# kombee.net
KiCad netlist of a schematic drawn in EAGLE
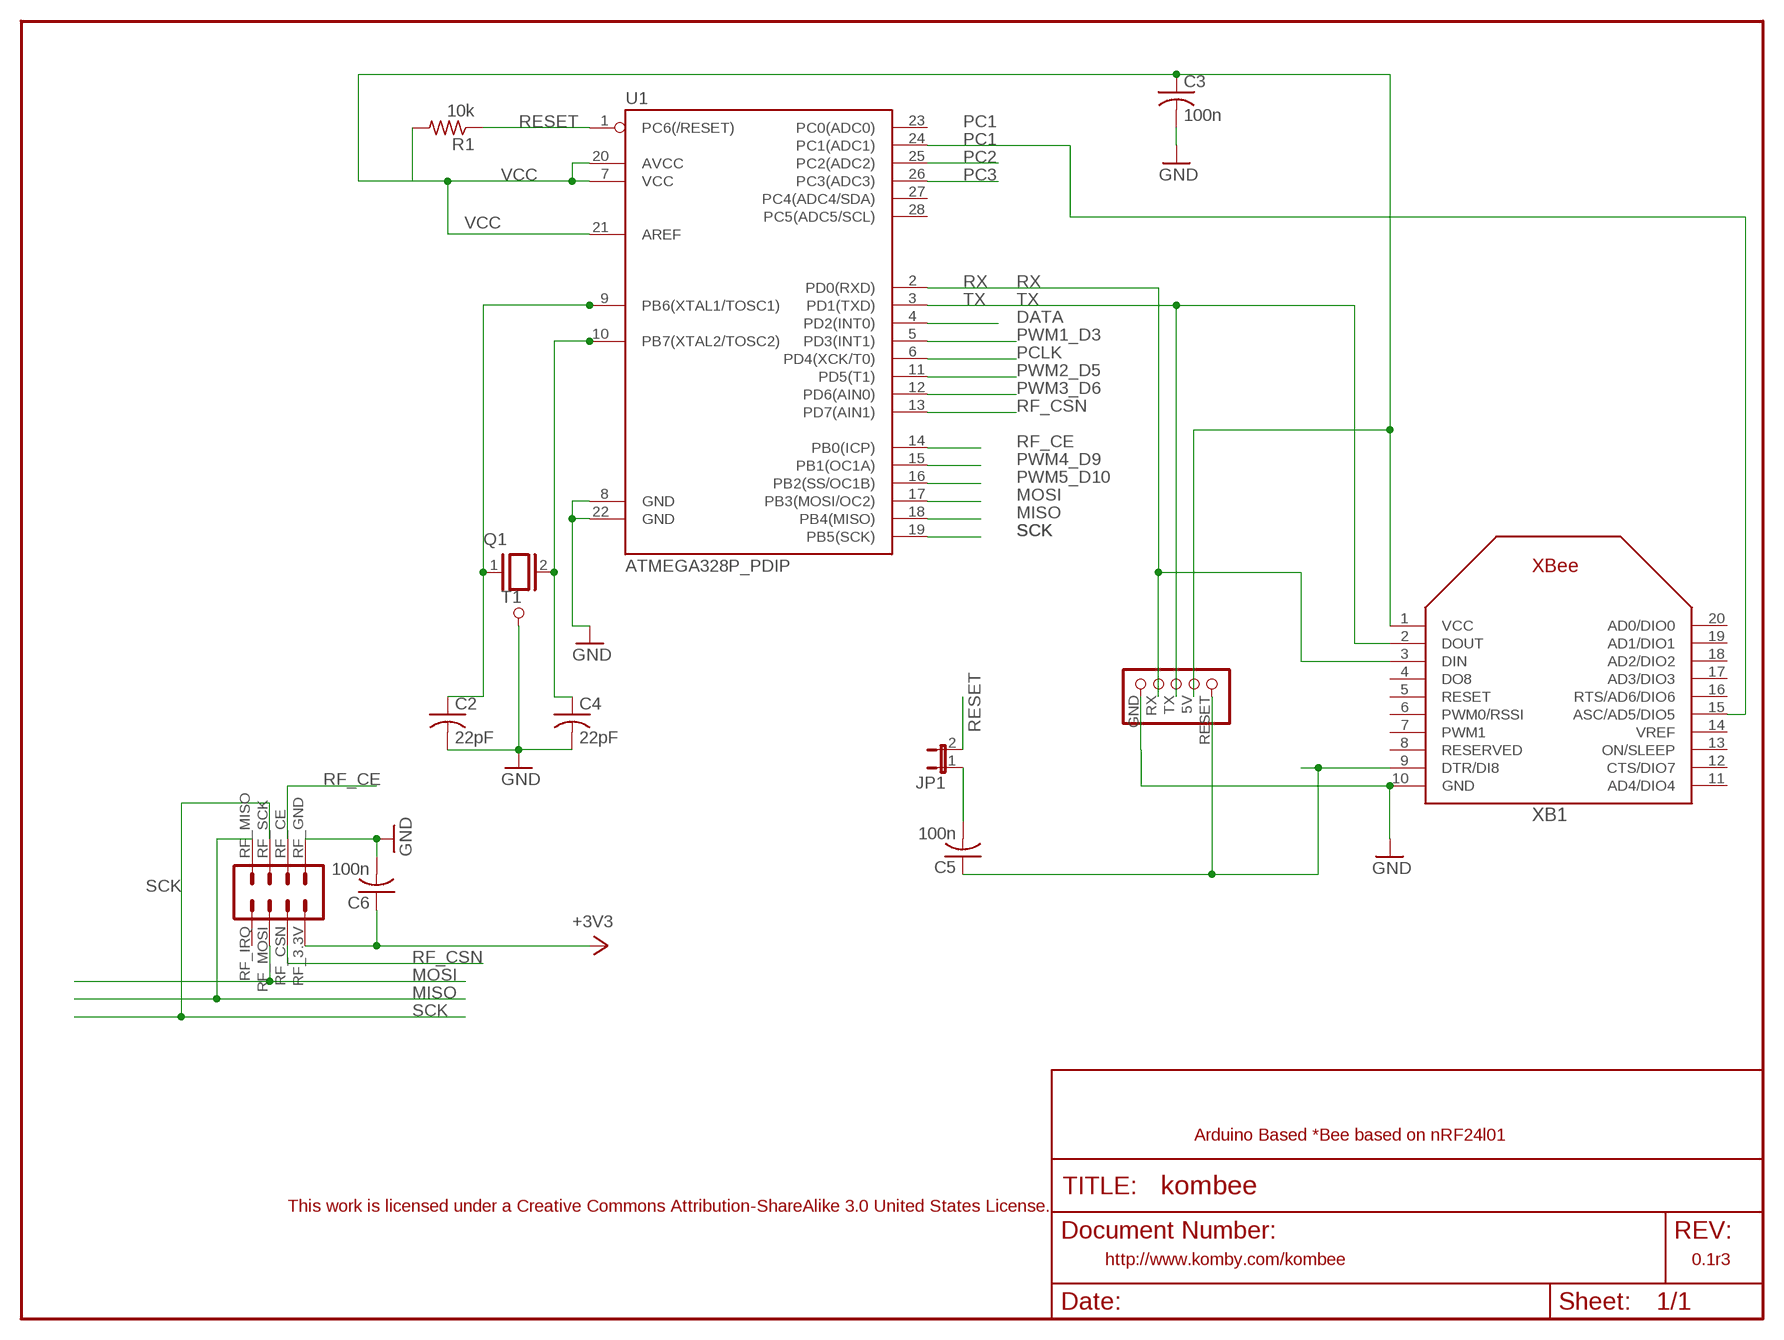
[diagram p0: schematic, sheet 1]

(export (version "E")
  (design (tool "Eeschema 10.0.6"))
  (components
    (comp (ref "C2")
      (value "22pF")
      (footprint "eagle-import:C0805K")
      (libsource (lib "eagle-import") (part "C-USC0805K"))
    )
    (comp (ref "C3")
      (value "100n")
      (footprint "eagle-import:C025-025X050")
      (libsource (lib "eagle-import") (part "C-US025-025X050"))
    )
    (comp (ref "C4")
      (value "22pF")
      (footprint "eagle-import:C0805K")
      (libsource (lib "eagle-import") (part "C-USC0805K"))
    )
    (comp (ref "C5")
      (value "100n")
      (footprint "eagle-import:C025-025X050")
      (libsource (lib "eagle-import") (part "C-US025-025X050"))
    )
    (comp (ref "C6")
      (value "100n")
      (footprint "eagle-import:C025-025X050")
      (libsource (lib "eagle-import") (part "C-US025-025X050"))
    )
    (comp (ref "JP1")
      (value "JP1E")
      (footprint "eagle-import:JP1")
      (libsource (lib "eagle-import") (part "JP1E"))
    )
    (comp (ref "Q1")
      (value "XTAL/S")
      (footprint "eagle-import:QS")
      (libsource (lib "eagle-import") (part "XTAL/S"))
    )
    (comp (ref "R1")
      (value "10k")
      (footprint "eagle-import:0204_7")
      (libsource (lib "eagle-import") (part "R-US_0204/7"))
    )
    (comp (ref "T1")
      (value "PAD_TERMINAL-1.02MM_ROUND")
      (footprint "eagle-import:CON_PAD_ROUND_1.02MM")
      (libsource (lib "eagle-import") (part "PAD_TERMINAL-1.02MM_ROUND"))
    )
    (comp (ref "U$1")
      (value "NRF24L01_HEADER")
      (footprint "eagle-import:NRF24L01")
      (libsource (lib "eagle-import") (part "NRF24L01_HEADER"))
    )
    (comp (ref "U$2")
      (value "KOMBY_TTL_SERIAL")
      (footprint "eagle-import:KOMBY_SERIAL_FOOTPRINT")
      (libsource (lib "eagle-import") (part "KOMBY_TTL_SERIAL"))
    )
    (comp (ref "U1")
      (value "ATMEGA328P_PDIP")
      (footprint "eagle-import:DIL28-3")
      (libsource (lib "eagle-import") (part "ATMEGA328P_PDIP"))
    )
    (comp (ref "XB1")
      (value "XBEE")
      (footprint "eagle-import:XBEE")
      (libsource (lib "eagle-import") (part "XBEE"))
    )
  )
  (nets
    (net (code "1") (name "+3V3") (class "Default")
      (node (ref "C3") (pin "1") (pinfunction "1_1") (pintype "passive"))
      (node (ref "C6") (pin "1") (pinfunction "1_1") (pintype "passive"))
      (node (ref "R1") (pin "2") (pinfunction "2_2") (pintype "passive"))
      (node (ref "U$1") (pin "RF_3.3V") (pinfunction "RF_3.3V_RF_3.3V") (pintype "passive"))
      (node (ref "U$2") (pin "5V") (pinfunction "5V_5V") (pintype "passive"))
      (node (ref "U1") (pin "20") (pinfunction "AVCC_20") (pintype "bidirectional"))
      (node (ref "U1") (pin "21") (pinfunction "AREF_21") (pintype "bidirectional"))
      (node (ref "U1") (pin "7") (pinfunction "VCC_7") (pintype "bidirectional"))
      (node (ref "XB1") (pin "1") (pinfunction "VCC_1") (pintype "power_in"))
    )
    (net (code "2") (name "/DATA") (class "Default")
      (node (ref "U1") (pin "4") (pinfunction "PD2(INT0)_4") (pintype "bidirectional"))
    )
    (net (code "3") (name "/MISO") (class "Default")
      (node (ref "U$1") (pin "RF_MISO") (pinfunction "RF_MISO_RF_MISO") (pintype "passive"))
      (node (ref "U1") (pin "18") (pinfunction "PB4(MISO)_18") (pintype "bidirectional"))
    )
    (net (code "4") (name "/MOSI") (class "Default")
      (node (ref "U$1") (pin "RF_MOSI") (pinfunction "RF_MOSI_RF_MOSI") (pintype "passive"))
      (node (ref "U1") (pin "17") (pinfunction "PB3(MOSI/OC2)_17") (pintype "bidirectional"))
    )
    (net (code "5") (name "/PC1") (class "Default")
      (node (ref "U1") (pin "24") (pinfunction "PC1(ADC1)_24") (pintype "bidirectional"))
      (node (ref "XB1") (pin "15") (pinfunction "ASC/AD5/DIO5_15") (pintype "bidirectional"))
    )
    (net (code "6") (name "/PC2") (class "Default")
      (node (ref "U1") (pin "25") (pinfunction "PC2(ADC2)_25") (pintype "bidirectional"))
    )
    (net (code "7") (name "/PC3") (class "Default")
      (node (ref "U1") (pin "26") (pinfunction "PC3(ADC3)_26") (pintype "bidirectional"))
    )
    (net (code "8") (name "/PCLK") (class "Default")
      (node (ref "U1") (pin "6") (pinfunction "PD4(XCK/T0)_6") (pintype "bidirectional"))
    )
    (net (code "9") (name "/PWM1_D3") (class "Default")
      (node (ref "U1") (pin "5") (pinfunction "PD3(INT1)_5") (pintype "bidirectional"))
    )
    (net (code "10") (name "/PWM2_D5") (class "Default")
      (node (ref "U1") (pin "11") (pinfunction "PD5(T1)_11") (pintype "bidirectional"))
    )
    (net (code "11") (name "/PWM3_D6") (class "Default")
      (node (ref "U1") (pin "12") (pinfunction "PD6(AIN0)_12") (pintype "bidirectional"))
    )
    (net (code "12") (name "/PWM4_D9") (class "Default")
      (node (ref "U1") (pin "15") (pinfunction "PB1(OC1A)_15") (pintype "bidirectional"))
    )
    (net (code "13") (name "/PWM5_D10") (class "Default")
      (node (ref "U1") (pin "16") (pinfunction "PB2(SS/OC1B)_16") (pintype "bidirectional"))
    )
    (net (code "14") (name "/RESET") (class "Default")
      (node (ref "JP1") (pin "2") (pinfunction "2_2") (pintype "passive"))
      (node (ref "R1") (pin "1") (pinfunction "1_1") (pintype "passive"))
      (node (ref "U1") (pin "1") (pinfunction "PC6(/RESET)_1") (pintype "bidirectional"))
    )
    (net (code "15") (name "/RF_CE") (class "Default")
      (node (ref "U$1") (pin "RF_CE") (pinfunction "RF_CE_RF_CE") (pintype "passive"))
      (node (ref "U1") (pin "14") (pinfunction "PB0(ICP)_14") (pintype "bidirectional"))
    )
    (net (code "16") (name "/RF_CSN") (class "Default")
      (node (ref "U$1") (pin "RF_CSN") (pinfunction "RF_CSN_RF_CSN") (pintype "passive"))
      (node (ref "U1") (pin "13") (pinfunction "PD7(AIN1)_13") (pintype "bidirectional"))
    )
    (net (code "17") (name "/RX") (class "Default")
      (node (ref "U$2") (pin "RX") (pinfunction "RX_RX") (pintype "passive"))
      (node (ref "U1") (pin "2") (pinfunction "PD0(RXD)_2") (pintype "bidirectional"))
      (node (ref "XB1") (pin "3") (pinfunction "DIN_3") (pintype "input"))
    )
    (net (code "18") (name "/SCK") (class "Default")
      (node (ref "U$1") (pin "RF_SCK") (pinfunction "RF_SCK_RF_SCK") (pintype "passive"))
      (node (ref "U1") (pin "19") (pinfunction "PB5(SCK)_19") (pintype "bidirectional"))
    )
    (net (code "19") (name "/TX") (class "Default")
      (node (ref "U$2") (pin "TX") (pinfunction "TX_TX") (pintype "passive"))
      (node (ref "U1") (pin "3") (pinfunction "PD1(TXD)_3") (pintype "bidirectional"))
      (node (ref "XB1") (pin "2") (pinfunction "DOUT_2") (pintype "output"))
    )
    (net (code "20") (name "GND") (class "Default")
      (node (ref "C2") (pin "2") (pinfunction "2_2") (pintype "passive"))
      (node (ref "C3") (pin "2") (pinfunction "2_2") (pintype "passive"))
      (node (ref "C4") (pin "2") (pinfunction "2_2") (pintype "passive"))
      (node (ref "C6") (pin "2") (pinfunction "2_2") (pintype "passive"))
      (node (ref "T1") (pin "P") (pinfunction "P_P") (pintype "passive"))
      (node (ref "U$1") (pin "RF_GND") (pinfunction "RFGND_1_RF_GND") (pintype "passive"))
      (node (ref "U$2") (pin "GND") (pinfunction "GND_GND") (pintype "passive"))
      (node (ref "U1") (pin "22") (pinfunction "GND_22") (pintype "bidirectional"))
      (node (ref "U1") (pin "8") (pinfunction "GND_8") (pintype "bidirectional"))
      (node (ref "XB1") (pin "10") (pinfunction "GND_10") (pintype "power_in"))
    )
    (net (code "21") (name "Net-(C5-Pad2)") (class "Default")
      (node (ref "C5") (pin "2") (pinfunction "2_2") (pintype "passive"))
      (node (ref "JP1") (pin "1") (pinfunction "1_1") (pintype "passive"))
    )
    (net (code "22") (name "Net-(U1-PB6(XTAL1{slash}TOSC1))") (class "Default")
      (node (ref "C2") (pin "1") (pinfunction "1_1") (pintype "passive"))
      (node (ref "Q1") (pin "1") (pinfunction "1_1") (pintype "passive"))
      (node (ref "U1") (pin "9") (pinfunction "PB6(XTAL1/TOSC1)_9") (pintype "bidirectional"))
    )
    (net (code "23") (name "Net-(U1-PB7(XTAL2{slash}TOSC2))") (class "Default")
      (node (ref "C4") (pin "1") (pinfunction "1_1") (pintype "passive"))
      (node (ref "Q1") (pin "2") (pinfunction "2_2") (pintype "passive"))
      (node (ref "U1") (pin "10") (pinfunction "PB7(XTAL2/TOSC2)_10") (pintype "bidirectional"))
    )
    (net (code "24") (name "Net-(XB1-DTR{slash}DI8)") (class "Default")
      (node (ref "C5") (pin "1") (pinfunction "1_1") (pintype "passive"))
      (node (ref "U$2") (pin "RESET") (pinfunction "RESET_RESET") (pintype "passive"))
      (node (ref "XB1") (pin "9") (pinfunction "DTR/DI8_9") (pintype "input"))
    )
    (net (code "25") (name "unconnected-(U$1-PadRF_IRQ)") (class "Default")
      (node (ref "U$1") (pin "RF_IRQ") (pinfunction "RF_IRQ_RF_IRQ") (pintype "passive"))
    )
    (net (code "26") (name "unconnected-(U1-PC0(ADC0)-Pad23)") (class "Default")
      (node (ref "U1") (pin "23") (pinfunction "PC0(ADC0)_23") (pintype "bidirectional"))
    )
    (net (code "27") (name "unconnected-(U1-PC4(ADC4{slash}SDA)-Pad27)") (class "Default")
      (node (ref "U1") (pin "27") (pinfunction "PC4(ADC4/SDA)_27") (pintype "bidirectional"))
    )
    (net (code "28") (name "unconnected-(U1-PC5(ADC5{slash}SCL)-Pad28)") (class "Default")
      (node (ref "U1") (pin "28") (pinfunction "PC5(ADC5/SCL)_28") (pintype "bidirectional"))
    )
    (net (code "29") (name "unconnected-(XB1-AD0{slash}DIO0-Pad20)") (class "Default")
      (node (ref "XB1") (pin "20") (pinfunction "AD0/DIO0_20") (pintype "bidirectional"))
    )
    (net (code "30") (name "unconnected-(XB1-AD1{slash}DIO1-Pad19)") (class "Default")
      (node (ref "XB1") (pin "19") (pinfunction "AD1/DIO1_19") (pintype "bidirectional"))
    )
    (net (code "31") (name "unconnected-(XB1-AD2{slash}DIO2-Pad18)") (class "Default")
      (node (ref "XB1") (pin "18") (pinfunction "AD2/DIO2_18") (pintype "bidirectional"))
    )
    (net (code "32") (name "unconnected-(XB1-AD3{slash}DIO3-Pad17)") (class "Default")
      (node (ref "XB1") (pin "17") (pinfunction "AD3/DIO3_17") (pintype "bidirectional"))
    )
    (net (code "33") (name "unconnected-(XB1-AD4{slash}DIO4-Pad11)") (class "Default")
      (node (ref "XB1") (pin "11") (pinfunction "AD4/DIO4_11") (pintype "bidirectional"))
    )
    (net (code "34") (name "unconnected-(XB1-CTS{slash}DIO7-Pad12)") (class "Default")
      (node (ref "XB1") (pin "12") (pinfunction "CTS/DIO7_12") (pintype "bidirectional"))
    )
    (net (code "35") (name "unconnected-(XB1-DO8-Pad4)") (class "Default")
      (node (ref "XB1") (pin "4") (pinfunction "DO8_4") (pintype "output"))
    )
    (net (code "36") (name "unconnected-(XB1-ON{slash}SLEEP-Pad13)") (class "Default")
      (node (ref "XB1") (pin "13") (pinfunction "ON/SLEEP_13") (pintype "output"))
    )
    (net (code "37") (name "unconnected-(XB1-PWM0{slash}RSSI-Pad6)") (class "Default")
      (node (ref "XB1") (pin "6") (pinfunction "PWM0/RSSI_6") (pintype "output"))
    )
    (net (code "38") (name "unconnected-(XB1-PWM1-Pad7)") (class "Default")
      (node (ref "XB1") (pin "7") (pinfunction "PWM1_7") (pintype "output"))
    )
    (net (code "39") (name "unconnected-(XB1-RESERVED-Pad8)") (class "Default")
      (node (ref "XB1") (pin "8") (pinfunction "RESERVED_8") (pintype "no_connect"))
    )
    (net (code "40") (name "unconnected-(XB1-RESET-Pad5)") (class "Default")
      (node (ref "XB1") (pin "5") (pinfunction "RESET_5") (pintype "input"))
    )
    (net (code "41") (name "unconnected-(XB1-RTS{slash}AD6{slash}DIO6-Pad16)") (class "Default")
      (node (ref "XB1") (pin "16") (pinfunction "RTS/AD6/DIO6_16") (pintype "bidirectional"))
    )
    (net (code "42") (name "unconnected-(XB1-VREF-Pad14)") (class "Default")
      (node (ref "XB1") (pin "14") (pinfunction "VREF_14") (pintype "input"))
    )
  )
)
